# miniDCU.net
KiCad netlist of a schematic drawn in EAGLE
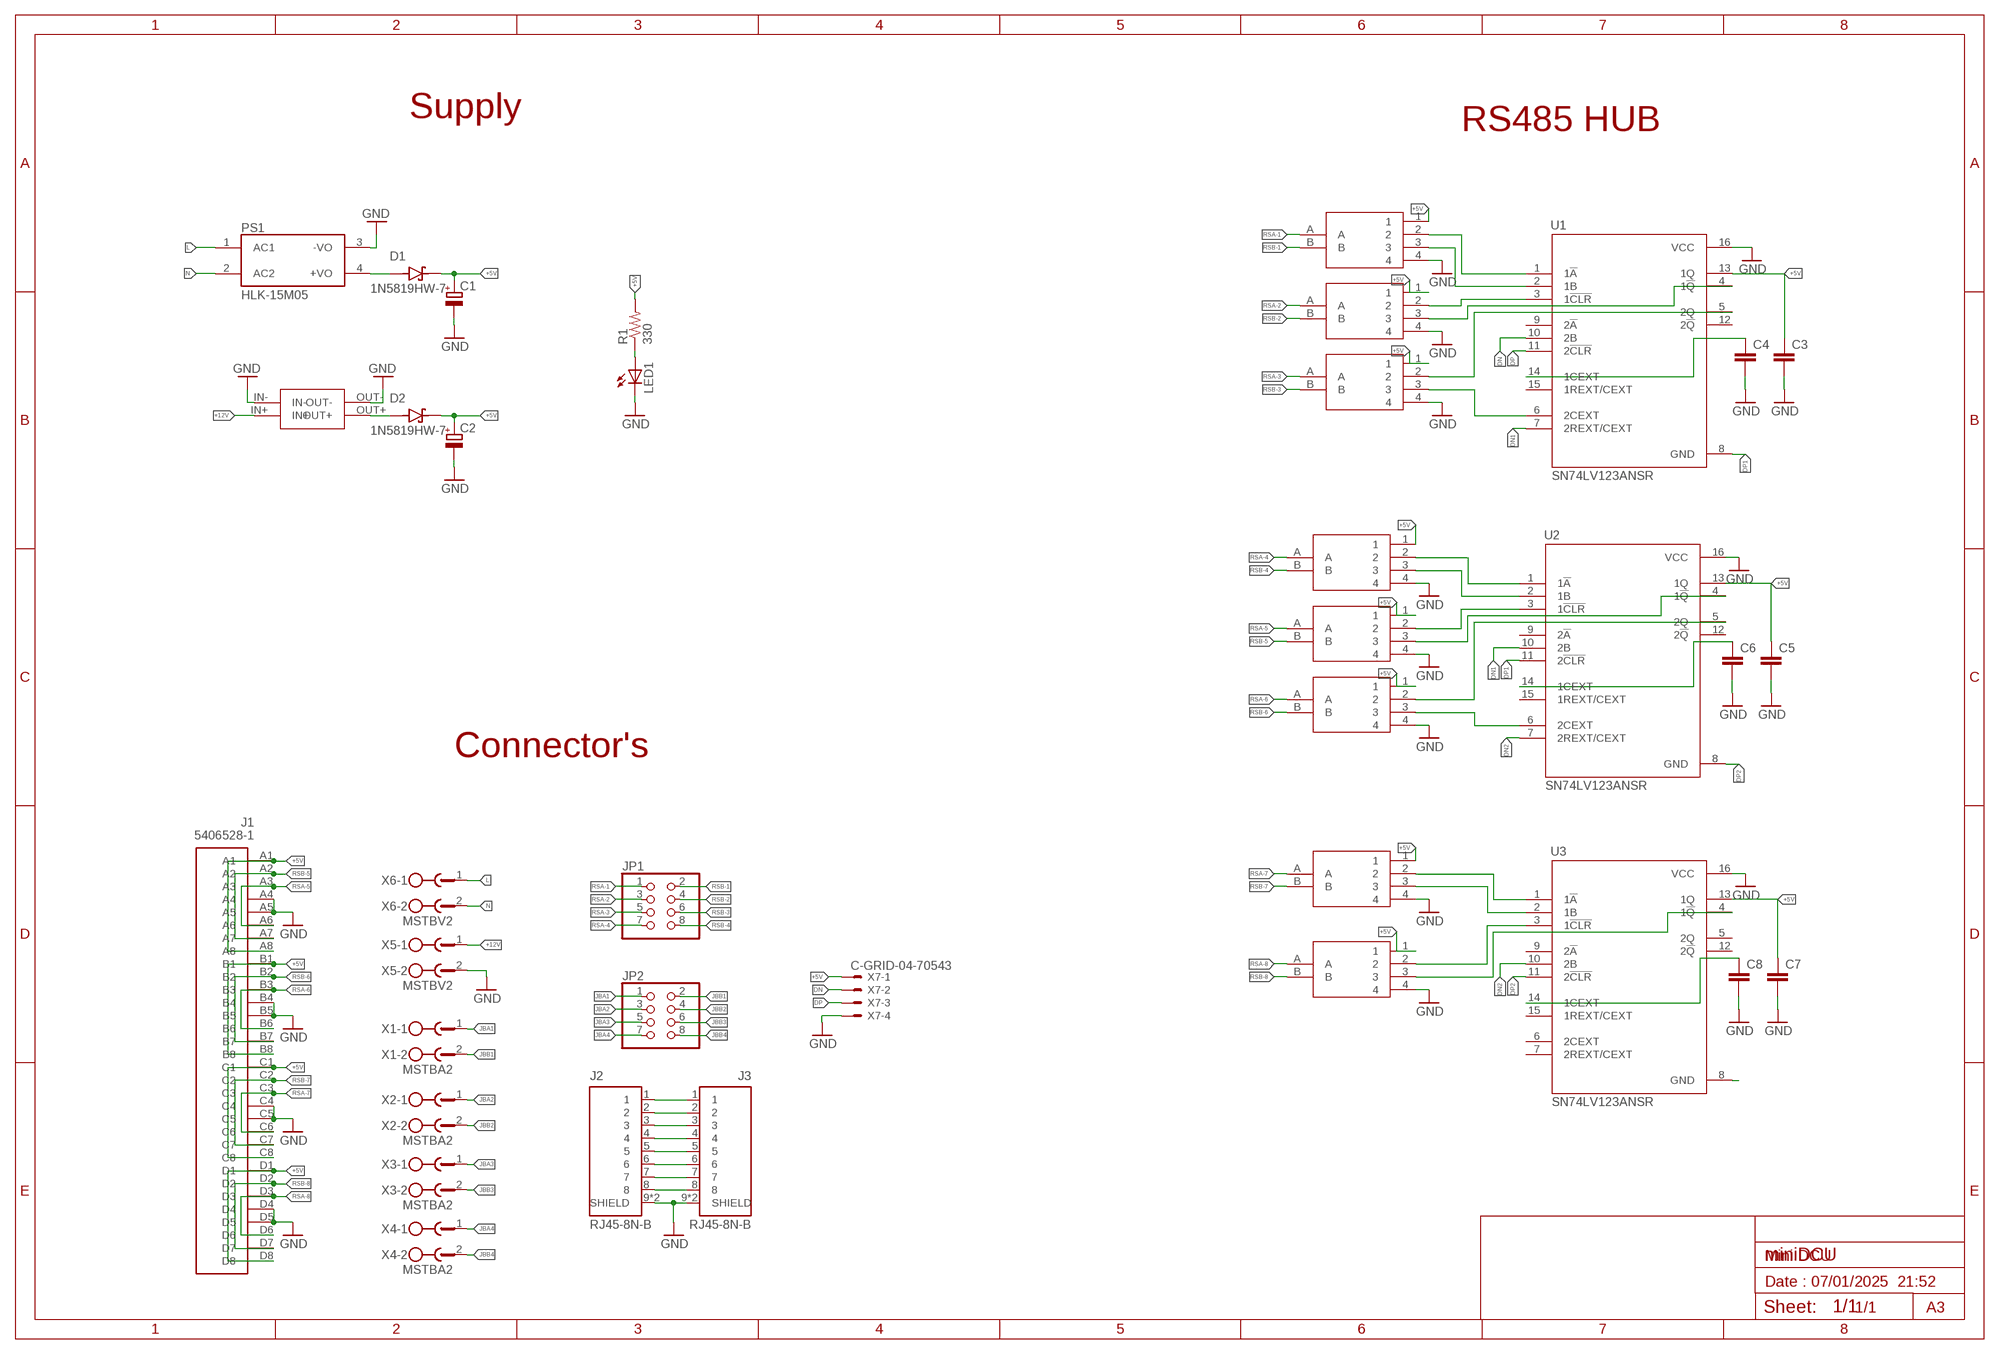
[diagram p0: schematic, sheet 1]

(export (version "E")
  (design (tool "Eeschema 10.0.6"))
  (components
    (comp (ref "C1")
      (value "CPOL-EU153CLV-0505")
      (footprint "eagle-import:153CLV-0505")
      (libsource (lib "eagle-import") (part "CPOL-EU153CLV-0505"))
    )
    (comp (ref "C2")
      (value "CPOL-EU153CLV-0505")
      (footprint "eagle-import:153CLV-0505")
      (libsource (lib "eagle-import") (part "CPOL-EU153CLV-0505"))
    )
    (comp (ref "C3")
      (value "C-EUC0603K")
      (footprint "eagle-import:C0603K")
      (libsource (lib "eagle-import") (part "C-EUC0603K"))
    )
    (comp (ref "C4")
      (value "C-EUC0603K")
      (footprint "eagle-import:C0603K")
      (libsource (lib "eagle-import") (part "C-EUC0603K"))
    )
    (comp (ref "C5")
      (value "C-EUC0603K")
      (footprint "eagle-import:C0603K")
      (libsource (lib "eagle-import") (part "C-EUC0603K"))
    )
    (comp (ref "C6")
      (value "C-EUC0603K")
      (footprint "eagle-import:C0603K")
      (libsource (lib "eagle-import") (part "C-EUC0603K"))
    )
    (comp (ref "C7")
      (value "C-EUC0603K")
      (footprint "eagle-import:C0603K")
      (libsource (lib "eagle-import") (part "C-EUC0603K"))
    )
    (comp (ref "C8")
      (value "C-EUC0603K")
      (footprint "eagle-import:C0603K")
      (libsource (lib "eagle-import") (part "C-EUC0603K"))
    )
    (comp (ref "D1")
      (value "1N5819HW-7")
      (footprint "eagle-import:SOD3715X145N")
      (fields (field (name "MF") "Diodes Inc."))
      (libsource (lib "eagle-import") (part "1N5819HW-7"))
    )
    (comp (ref "D2")
      (value "1N5819HW-7")
      (footprint "eagle-import:SOD3715X145N")
      (fields (field (name "MF") "Diodes Inc."))
      (libsource (lib "eagle-import") (part "1N5819HW-7"))
    )
    (comp (ref "J1")
      (value "5406528-1")
      (footprint "eagle-import:5406528-1")
      (fields (field (name "MF") "TE Connectivity"))
      (libsource (lib "eagle-import") (part "5406528-1"))
    )
    (comp (ref "J2")
      (value "RJ45-8N-B")
      (footprint "eagle-import:TE_RJ45-8N-B")
      (fields (field (name "MF") "TE Connectivity"))
      (libsource (lib "eagle-import") (part "RJ45-8N-B"))
    )
    (comp (ref "J3")
      (value "RJ45-8N-B")
      (footprint "eagle-import:TE_RJ45-8N-B")
      (fields (field (name "MF") "TE Connectivity"))
      (libsource (lib "eagle-import") (part "RJ45-8N-B"))
    )
    (comp (ref "JP1")
      (value "PINHD-2X4")
      (footprint "eagle-import:2X04")
      (libsource (lib "eagle-import") (part "PINHD-2X4"))
    )
    (comp (ref "JP2")
      (value "PINHD-2X4")
      (footprint "eagle-import:2X04")
      (libsource (lib "eagle-import") (part "PINHD-2X4"))
    )
    (comp (ref "LED1")
      (value "LED3MM")
      (footprint "eagle-import:LED3MM")
      (libsource (lib "eagle-import") (part "LED3MM"))
    )
    (comp (ref "MINI1")
      (value "MINI360")
      (footprint "eagle-import:MINI360")
      (libsource (lib "eagle-import") (part "MINI360"))
    )
    (comp (ref "PS1")
      (value "HLK-15M05")
      (footprint "eagle-import:CONV_HLK-15M05")
      (fields (field (name "MF") "Hi-link") (field (name "MP") "HLK-10M12"))
      (libsource (lib "eagle-import") (part "HLK-15M05"))
    )
    (comp (ref "R1")
      (value "330")
      (footprint "eagle-import:M0805")
      (libsource (lib "eagle-import") (part "R-US_M0805"))
    )
    (comp (ref "U1")
      (value "SN74LV123ANSR")
      (footprint "eagle-import:SOIC127P780X200-16N")
      (fields (field (name "DIGIKEY_PART_NUMBER") "296-46201-2-ND") (field (name "MF") "Texas Instruments"))
      (libsource (lib "eagle-import") (part "SN74LV123ANSR"))
    )
    (comp (ref "U2")
      (value "SN74LV123ANSR")
      (footprint "eagle-import:SOIC127P780X200-16N")
      (fields (field (name "DIGIKEY_PART_NUMBER") "296-46201-2-ND") (field (name "MF") "Texas Instruments"))
      (libsource (lib "eagle-import") (part "SN74LV123ANSR"))
    )
    (comp (ref "U3")
      (value "SN74LV123ANSR")
      (footprint "eagle-import:SOIC127P780X200-16N")
      (fields (field (name "DIGIKEY_PART_NUMBER") "296-46201-2-ND") (field (name "MF") "Texas Instruments"))
      (libsource (lib "eagle-import") (part "SN74LV123ANSR"))
    )
    (comp (ref "USB2RS1")
      (value "USB2RS485")
      (footprint "eagle-import:USB2RS485")
      (libsource (lib "eagle-import") (part "USB2RS485"))
    )
    (comp (ref "USB2RS2")
      (value "USB2RS485")
      (footprint "eagle-import:USB2RS485")
      (libsource (lib "eagle-import") (part "USB2RS485"))
    )
    (comp (ref "USB2RS3")
      (value "USB2RS485")
      (footprint "eagle-import:USB2RS485")
      (libsource (lib "eagle-import") (part "USB2RS485"))
    )
    (comp (ref "USB2RS4")
      (value "USB2RS485")
      (footprint "eagle-import:USB2RS485")
      (libsource (lib "eagle-import") (part "USB2RS485"))
    )
    (comp (ref "USB2RS5")
      (value "USB2RS485")
      (footprint "eagle-import:USB2RS485")
      (libsource (lib "eagle-import") (part "USB2RS485"))
    )
    (comp (ref "USB2RS6")
      (value "USB2RS485")
      (footprint "eagle-import:USB2RS485")
      (libsource (lib "eagle-import") (part "USB2RS485"))
    )
    (comp (ref "USB2RS7")
      (value "USB2RS485")
      (footprint "eagle-import:USB2RS485")
      (libsource (lib "eagle-import") (part "USB2RS485"))
    )
    (comp (ref "USB2RS8")
      (value "USB2RS485")
      (footprint "eagle-import:USB2RS485")
      (libsource (lib "eagle-import") (part "USB2RS485"))
    )
    (comp (ref "X1")
      (value "MSTBA2")
      (footprint "eagle-import:MSTBA2")
      (fields (field (name "MF") "FARNELL") (field (name "MPN") "1757242"))
      (libsource (lib "eagle-import") (part "MSTBA2"))
    )
    (comp (ref "X2")
      (value "MSTBA2")
      (footprint "eagle-import:MSTBA2")
      (fields (field (name "MF") "FARNELL") (field (name "MPN") "1757242"))
      (libsource (lib "eagle-import") (part "MSTBA2"))
    )
    (comp (ref "X3")
      (value "MSTBA2")
      (footprint "eagle-import:MSTBA2")
      (fields (field (name "MF") "FARNELL") (field (name "MPN") "1757242"))
      (libsource (lib "eagle-import") (part "MSTBA2"))
    )
    (comp (ref "X4")
      (value "MSTBA2")
      (footprint "eagle-import:MSTBA2")
      (fields (field (name "MF") "FARNELL") (field (name "MPN") "1757242"))
      (libsource (lib "eagle-import") (part "MSTBA2"))
    )
    (comp (ref "X5")
      (value "MSTBV2")
      (footprint "eagle-import:MSTBV2")
      (libsource (lib "eagle-import") (part "MSTBV2"))
    )
    (comp (ref "X6")
      (value "MSTBV2")
      (footprint "eagle-import:MSTBV2")
      (libsource (lib "eagle-import") (part "MSTBV2"))
    )
    (comp (ref "X7")
      (value "C-GRID-04-70543")
      (footprint "eagle-import:70543-04")
      (fields (field (name "MF") "MOLEX"))
      (libsource (lib "eagle-import") (part "C-GRID-04-70543"))
    )
  )
  (nets
    (net (code "1") (name "+5V") (class "Default")
      (node (ref "C1") (pin "+") (pinfunction "+_+") (pintype "passive"))
      (node (ref "C2") (pin "+") (pinfunction "+_+") (pintype "passive"))
      (node (ref "C3") (pin "1") (pinfunction "1_1") (pintype "passive"))
      (node (ref "C5") (pin "1") (pinfunction "1_1") (pintype "passive"))
      (node (ref "C7") (pin "1") (pinfunction "1_1") (pintype "passive"))
      (node (ref "D1") (pin "C") (pinfunction "K_C") (pintype "passive"))
      (node (ref "D2") (pin "C") (pinfunction "K_C") (pintype "passive"))
      (node (ref "J1") (pin "A1") (pinfunction "A1_A1") (pintype "bidirectional"))
      (node (ref "J1") (pin "A8") (pinfunction "A8_A8") (pintype "bidirectional"))
      (node (ref "J1") (pin "B1") (pinfunction "B1_B1") (pintype "bidirectional"))
      (node (ref "J1") (pin "B8") (pinfunction "B8_B8") (pintype "bidirectional"))
      (node (ref "J1") (pin "C1") (pinfunction "C1_C1") (pintype "bidirectional"))
      (node (ref "J1") (pin "C8") (pinfunction "C8_C8") (pintype "bidirectional"))
      (node (ref "J1") (pin "D1") (pinfunction "D1_D1") (pintype "bidirectional"))
      (node (ref "J1") (pin "D8") (pinfunction "D8_D8") (pintype "bidirectional"))
      (node (ref "R1") (pin "2") (pinfunction "2_2") (pintype "passive"))
      (node (ref "U1") (pin "13") (pinfunction "1Q_13") (pintype "output"))
      (node (ref "U2") (pin "13") (pinfunction "1Q_13") (pintype "output"))
      (node (ref "U3") (pin "13") (pinfunction "1Q_13") (pintype "output"))
      (node (ref "USB2RS1") (pin "1") (pinfunction "1_1") (pintype "bidirectional"))
      (node (ref "USB2RS2") (pin "1") (pinfunction "1_1") (pintype "bidirectional"))
      (node (ref "USB2RS3") (pin "1") (pinfunction "1_1") (pintype "bidirectional"))
      (node (ref "USB2RS4") (pin "1") (pinfunction "1_1") (pintype "bidirectional"))
      (node (ref "USB2RS5") (pin "1") (pinfunction "1_1") (pintype "bidirectional"))
      (node (ref "USB2RS6") (pin "1") (pinfunction "1_1") (pintype "bidirectional"))
      (node (ref "USB2RS7") (pin "1") (pinfunction "1_1") (pintype "bidirectional"))
      (node (ref "USB2RS8") (pin "1") (pinfunction "1_1") (pintype "bidirectional"))
      (node (ref "X7") (pin "1") (pinfunction "S_1") (pintype "passive"))
    )
    (net (code "2") (name "+12V") (class "Default")
      (node (ref "MINI1") (pin "IN+") (pinfunction "IN+_IN+") (pintype "bidirectional"))
      (node (ref "X5") (pin "1") (pinfunction "1_1") (pintype "passive"))
    )
    (net (code "3") (name "DN") (class "Default")
      (node (ref "U1") (pin "10") (pinfunction "2B_10") (pintype "input"))
      (node (ref "X7") (pin "2") (pinfunction "S_2") (pintype "passive"))
    )
    (net (code "4") (name "DN1") (class "Default")
      (node (ref "U1") (pin "7") (pinfunction "2REXT/CEXT_7") (pintype "bidirectional"))
      (node (ref "U2") (pin "10") (pinfunction "2B_10") (pintype "input"))
    )
    (net (code "5") (name "DN2") (class "Default")
      (node (ref "U2") (pin "7") (pinfunction "2REXT/CEXT_7") (pintype "bidirectional"))
      (node (ref "U3") (pin "10") (pinfunction "2B_10") (pintype "input"))
    )
    (net (code "6") (name "DP") (class "Default")
      (node (ref "U1") (pin "11") (pinfunction "2~{CLR}_11") (pintype "input"))
      (node (ref "X7") (pin "3") (pinfunction "S_3") (pintype "passive"))
    )
    (net (code "7") (name "DP1") (class "Default")
      (node (ref "U1") (pin "8") (pinfunction "GND_8") (pintype "power_in"))
      (node (ref "U2") (pin "11") (pinfunction "2~{CLR}_11") (pintype "input"))
    )
    (net (code "8") (name "DP2") (class "Default")
      (node (ref "U2") (pin "8") (pinfunction "GND_8") (pintype "power_in"))
      (node (ref "U3") (pin "11") (pinfunction "2~{CLR}_11") (pintype "input"))
    )
    (net (code "9") (name "GND") (class "Default")
      (node (ref "C1") (pin "-") (pinfunction "-_-") (pintype "passive"))
      (node (ref "C2") (pin "-") (pinfunction "-_-") (pintype "passive"))
      (node (ref "C3") (pin "2") (pinfunction "2_2") (pintype "passive"))
      (node (ref "C4") (pin "2") (pinfunction "2_2") (pintype "passive"))
      (node (ref "C5") (pin "2") (pinfunction "2_2") (pintype "passive"))
      (node (ref "C6") (pin "2") (pinfunction "2_2") (pintype "passive"))
      (node (ref "C7") (pin "2") (pinfunction "2_2") (pintype "passive"))
      (node (ref "C8") (pin "2") (pinfunction "2_2") (pintype "passive"))
      (node (ref "J1") (pin "A4") (pinfunction "A4_A4") (pintype "bidirectional"))
      (node (ref "J1") (pin "A5") (pinfunction "A5_A5") (pintype "bidirectional"))
      (node (ref "J1") (pin "B4") (pinfunction "B4_B4") (pintype "bidirectional"))
      (node (ref "J1") (pin "B5") (pinfunction "B5_B5") (pintype "bidirectional"))
      (node (ref "J1") (pin "C4") (pinfunction "C4_C4") (pintype "bidirectional"))
      (node (ref "J1") (pin "C5") (pinfunction "C5_C5") (pintype "bidirectional"))
      (node (ref "J1") (pin "D4") (pinfunction "D4_D4") (pintype "bidirectional"))
      (node (ref "J1") (pin "D5") (pinfunction "D5_D5") (pintype "bidirectional"))
      (node (ref "J2") (pin "10") (pinfunction "SHIELD_10") (pintype "passive"))
      (node (ref "J2") (pin "9") (pinfunction "SHIELD_9") (pintype "passive"))
      (node (ref "J3") (pin "10") (pinfunction "SHIELD_10") (pintype "passive"))
      (node (ref "J3") (pin "9") (pinfunction "SHIELD_9") (pintype "passive"))
      (node (ref "LED1") (pin "K") (pinfunction "C_K") (pintype "passive"))
      (node (ref "MINI1") (pin "IN-") (pinfunction "IN-_IN-") (pintype "bidirectional"))
      (node (ref "MINI1") (pin "OUT-") (pinfunction "OUT-_OUT-") (pintype "bidirectional"))
      (node (ref "PS1") (pin "3") (pinfunction "-VO_3") (pintype "output"))
      (node (ref "U1") (pin "16") (pinfunction "VCC_16") (pintype "power_in"))
      (node (ref "U2") (pin "16") (pinfunction "VCC_16") (pintype "power_in"))
      (node (ref "U3") (pin "16") (pinfunction "VCC_16") (pintype "power_in"))
      (node (ref "USB2RS1") (pin "4") (pinfunction "4_4") (pintype "bidirectional"))
      (node (ref "USB2RS2") (pin "4") (pinfunction "4_4") (pintype "bidirectional"))
      (node (ref "USB2RS3") (pin "4") (pinfunction "4_4") (pintype "bidirectional"))
      (node (ref "USB2RS4") (pin "4") (pinfunction "4_4") (pintype "bidirectional"))
      (node (ref "USB2RS5") (pin "4") (pinfunction "4_4") (pintype "bidirectional"))
      (node (ref "USB2RS6") (pin "4") (pinfunction "4_4") (pintype "bidirectional"))
      (node (ref "USB2RS7") (pin "4") (pinfunction "4_4") (pintype "bidirectional"))
      (node (ref "USB2RS8") (pin "4") (pinfunction "4_4") (pintype "bidirectional"))
      (node (ref "X5") (pin "2") (pinfunction "1_2") (pintype "passive"))
      (node (ref "X7") (pin "4") (pinfunction "S_4") (pintype "passive"))
    )
    (net (code "10") (name "JBA1") (class "Default")
      (node (ref "JP2") (pin "1") (pinfunction "1_1") (pintype "passive"))
      (node (ref "X1") (pin "1") (pinfunction "1_1") (pintype "passive"))
    )
    (net (code "11") (name "JBA2") (class "Default")
      (node (ref "JP2") (pin "3") (pinfunction "3_3") (pintype "passive"))
      (node (ref "X2") (pin "1") (pinfunction "1_1") (pintype "passive"))
    )
    (net (code "12") (name "JBA3") (class "Default")
      (node (ref "JP2") (pin "5") (pinfunction "5_5") (pintype "passive"))
      (node (ref "X3") (pin "1") (pinfunction "1_1") (pintype "passive"))
    )
    (net (code "13") (name "JBA4") (class "Default")
      (node (ref "JP2") (pin "7") (pinfunction "7_7") (pintype "passive"))
      (node (ref "X4") (pin "1") (pinfunction "1_1") (pintype "passive"))
    )
    (net (code "14") (name "JBB1") (class "Default")
      (node (ref "JP2") (pin "2") (pinfunction "2_2") (pintype "passive"))
      (node (ref "X1") (pin "2") (pinfunction "1_2") (pintype "passive"))
    )
    (net (code "15") (name "JBB2") (class "Default")
      (node (ref "JP2") (pin "4") (pinfunction "4_4") (pintype "passive"))
      (node (ref "X2") (pin "2") (pinfunction "1_2") (pintype "passive"))
    )
    (net (code "16") (name "JBB3") (class "Default")
      (node (ref "JP2") (pin "6") (pinfunction "6_6") (pintype "passive"))
      (node (ref "X3") (pin "2") (pinfunction "1_2") (pintype "passive"))
    )
    (net (code "17") (name "JBB4") (class "Default")
      (node (ref "JP2") (pin "8") (pinfunction "8_8") (pintype "passive"))
      (node (ref "X4") (pin "2") (pinfunction "1_2") (pintype "passive"))
    )
    (net (code "18") (name "L") (class "Default")
      (node (ref "PS1") (pin "1") (pinfunction "AC1_1") (pintype "input"))
      (node (ref "X6") (pin "1") (pinfunction "1_1") (pintype "passive"))
    )
    (net (code "19") (name "N") (class "Default")
      (node (ref "PS1") (pin "2") (pinfunction "AC2_2") (pintype "input"))
      (node (ref "X6") (pin "2") (pinfunction "1_2") (pintype "passive"))
    )
    (net (code "20") (name "Net-(D2-PadA)") (class "Default")
      (node (ref "D2") (pin "A") (pinfunction "A_A") (pintype "passive"))
      (node (ref "MINI1") (pin "OUT+") (pinfunction "OUT+_OUT+") (pintype "bidirectional"))
    )
    (net (code "21") (name "Net-(J2-Pad1)") (class "Default")
      (node (ref "J2") (pin "1") (pinfunction "1_1") (pintype "passive"))
      (node (ref "J3") (pin "1") (pinfunction "1_1") (pintype "passive"))
    )
    (net (code "22") (name "Net-(J2-Pad2)") (class "Default")
      (node (ref "J2") (pin "2") (pinfunction "2_2") (pintype "passive"))
      (node (ref "J3") (pin "2") (pinfunction "2_2") (pintype "passive"))
    )
    (net (code "23") (name "Net-(J2-Pad3)") (class "Default")
      (node (ref "J2") (pin "3") (pinfunction "3_3") (pintype "passive"))
      (node (ref "J3") (pin "3") (pinfunction "3_3") (pintype "passive"))
    )
    (net (code "24") (name "Net-(J2-Pad4)") (class "Default")
      (node (ref "J2") (pin "4") (pinfunction "4_4") (pintype "passive"))
      (node (ref "J3") (pin "4") (pinfunction "4_4") (pintype "passive"))
    )
    (net (code "25") (name "Net-(J2-Pad5)") (class "Default")
      (node (ref "J2") (pin "5") (pinfunction "5_5") (pintype "passive"))
      (node (ref "J3") (pin "5") (pinfunction "5_5") (pintype "passive"))
    )
    (net (code "26") (name "Net-(J2-Pad6)") (class "Default")
      (node (ref "J2") (pin "6") (pinfunction "6_6") (pintype "passive"))
      (node (ref "J3") (pin "6") (pinfunction "6_6") (pintype "passive"))
    )
    (net (code "27") (name "Net-(J2-Pad7)") (class "Default")
      (node (ref "J2") (pin "7") (pinfunction "7_7") (pintype "passive"))
      (node (ref "J3") (pin "7") (pinfunction "7_7") (pintype "passive"))
    )
    (net (code "28") (name "Net-(J2-Pad8)") (class "Default")
      (node (ref "J2") (pin "8") (pinfunction "8_8") (pintype "passive"))
      (node (ref "J3") (pin "8") (pinfunction "8_8") (pintype "passive"))
    )
    (net (code "29") (name "Net-(LED1-PadA)") (class "Default")
      (node (ref "LED1") (pin "A") (pinfunction "A_A") (pintype "passive"))
      (node (ref "R1") (pin "1") (pinfunction "1_1") (pintype "passive"))
    )
    (net (code "30") (name "Net-(PS1-+VO)") (class "Default")
      (node (ref "D1") (pin "A") (pinfunction "A_A") (pintype "passive"))
      (node (ref "PS1") (pin "4") (pinfunction "+VO_4") (pintype "output"))
    )
    (net (code "31") (name "Net-(U1-1B)") (class "Default")
      (node (ref "U1") (pin "2") (pinfunction "1B_2") (pintype "input"))
      (node (ref "USB2RS1") (pin "3") (pinfunction "3_3") (pintype "bidirectional"))
    )
    (net (code "32") (name "Net-(U1-1CEXT)") (class "Default")
      (node (ref "C4") (pin "1") (pinfunction "1_1") (pintype "passive"))
      (node (ref "U1") (pin "14") (pinfunction "1CEXT_14") (pintype "bidirectional"))
    )
    (net (code "33") (name "Net-(U1-1~{A})") (class "Default")
      (node (ref "U1") (pin "1") (pinfunction "1~{A}_1") (pintype "input"))
      (node (ref "USB2RS1") (pin "2") (pinfunction "2_2") (pintype "bidirectional"))
    )
    (net (code "34") (name "Net-(U1-1~{CLR})") (class "Default")
      (node (ref "U1") (pin "3") (pinfunction "1~{CLR}_3") (pintype "input"))
      (node (ref "USB2RS2") (pin "2") (pinfunction "2_2") (pintype "bidirectional"))
    )
    (net (code "35") (name "Net-(U1-1~{Q})") (class "Default")
      (node (ref "U1") (pin "4") (pinfunction "1~{Q}_4") (pintype "output"))
      (node (ref "USB2RS2") (pin "3") (pinfunction "3_3") (pintype "bidirectional"))
    )
    (net (code "36") (name "Net-(U1-2CEXT)") (class "Default")
      (node (ref "U1") (pin "6") (pinfunction "2CEXT_6") (pintype "bidirectional"))
      (node (ref "USB2RS3") (pin "3") (pinfunction "3_3") (pintype "bidirectional"))
    )
    (net (code "37") (name "Net-(U1-2Q)") (class "Default")
      (node (ref "U1") (pin "5") (pinfunction "2Q_5") (pintype "output"))
      (node (ref "USB2RS3") (pin "2") (pinfunction "2_2") (pintype "bidirectional"))
    )
    (net (code "38") (name "Net-(U2-1B)") (class "Default")
      (node (ref "U2") (pin "2") (pinfunction "1B_2") (pintype "input"))
      (node (ref "USB2RS5") (pin "3") (pinfunction "3_3") (pintype "bidirectional"))
    )
    (net (code "39") (name "Net-(U2-1CEXT)") (class "Default")
      (node (ref "C6") (pin "1") (pinfunction "1_1") (pintype "passive"))
      (node (ref "U2") (pin "14") (pinfunction "1CEXT_14") (pintype "bidirectional"))
    )
    (net (code "40") (name "Net-(U2-1~{A})") (class "Default")
      (node (ref "U2") (pin "1") (pinfunction "1~{A}_1") (pintype "input"))
      (node (ref "USB2RS5") (pin "2") (pinfunction "2_2") (pintype "bidirectional"))
    )
    (net (code "41") (name "Net-(U2-1~{CLR})") (class "Default")
      (node (ref "U2") (pin "3") (pinfunction "1~{CLR}_3") (pintype "input"))
      (node (ref "USB2RS6") (pin "2") (pinfunction "2_2") (pintype "bidirectional"))
    )
    (net (code "42") (name "Net-(U2-1~{Q})") (class "Default")
      (node (ref "U2") (pin "4") (pinfunction "1~{Q}_4") (pintype "output"))
      (node (ref "USB2RS6") (pin "3") (pinfunction "3_3") (pintype "bidirectional"))
    )
    (net (code "43") (name "Net-(U2-2CEXT)") (class "Default")
      (node (ref "U2") (pin "6") (pinfunction "2CEXT_6") (pintype "bidirectional"))
      (node (ref "USB2RS7") (pin "3") (pinfunction "3_3") (pintype "bidirectional"))
    )
    (net (code "44") (name "Net-(U2-2Q)") (class "Default")
      (node (ref "U2") (pin "5") (pinfunction "2Q_5") (pintype "output"))
      (node (ref "USB2RS7") (pin "2") (pinfunction "2_2") (pintype "bidirectional"))
    )
    (net (code "45") (name "Net-(U3-1B)") (class "Default")
      (node (ref "U3") (pin "2") (pinfunction "1B_2") (pintype "input"))
      (node (ref "USB2RS4") (pin "3") (pinfunction "3_3") (pintype "bidirectional"))
    )
    (net (code "46") (name "Net-(U3-1CEXT)") (class "Default")
      (node (ref "C8") (pin "1") (pinfunction "1_1") (pintype "passive"))
      (node (ref "U3") (pin "14") (pinfunction "1CEXT_14") (pintype "bidirectional"))
    )
    (net (code "47") (name "Net-(U3-1~{A})") (class "Default")
      (node (ref "U3") (pin "1") (pinfunction "1~{A}_1") (pintype "input"))
      (node (ref "USB2RS4") (pin "2") (pinfunction "2_2") (pintype "bidirectional"))
    )
    (net (code "48") (name "Net-(U3-1~{CLR})") (class "Default")
      (node (ref "U3") (pin "3") (pinfunction "1~{CLR}_3") (pintype "input"))
      (node (ref "USB2RS8") (pin "2") (pinfunction "2_2") (pintype "bidirectional"))
    )
    (net (code "49") (name "Net-(U3-1~{Q})") (class "Default")
      (node (ref "U3") (pin "4") (pinfunction "1~{Q}_4") (pintype "output"))
      (node (ref "USB2RS8") (pin "3") (pinfunction "3_3") (pintype "bidirectional"))
    )
    (net (code "50") (name "RSA-1") (class "Default")
      (node (ref "JP1") (pin "1") (pinfunction "1_1") (pintype "passive"))
      (node (ref "USB2RS1") (pin "A") (pinfunction "A_A") (pintype "bidirectional"))
    )
    (net (code "51") (name "RSA-2") (class "Default")
      (node (ref "JP1") (pin "3") (pinfunction "3_3") (pintype "passive"))
      (node (ref "USB2RS2") (pin "A") (pinfunction "A_A") (pintype "bidirectional"))
    )
    (net (code "52") (name "RSA-3") (class "Default")
      (node (ref "JP1") (pin "5") (pinfunction "5_5") (pintype "passive"))
      (node (ref "USB2RS3") (pin "A") (pinfunction "A_A") (pintype "bidirectional"))
    )
    (net (code "53") (name "RSA-4") (class "Default")
      (node (ref "JP1") (pin "7") (pinfunction "7_7") (pintype "passive"))
      (node (ref "USB2RS5") (pin "A") (pinfunction "A_A") (pintype "bidirectional"))
    )
    (net (code "54") (name "RSA-5") (class "Default")
      (node (ref "J1") (pin "A3") (pinfunction "A3_A3") (pintype "bidirectional"))
      (node (ref "J1") (pin "A6") (pinfunction "A6_A6") (pintype "bidirectional"))
      (node (ref "USB2RS6") (pin "A") (pinfunction "A_A") (pintype "bidirectional"))
    )
    (net (code "55") (name "RSA-6") (class "Default")
      (node (ref "J1") (pin "B3") (pinfunction "B3_B3") (pintype "bidirectional"))
      (node (ref "J1") (pin "B6") (pinfunction "B6_B6") (pintype "bidirectional"))
      (node (ref "USB2RS7") (pin "A") (pinfunction "A_A") (pintype "bidirectional"))
    )
    (net (code "56") (name "RSA-7") (class "Default")
      (node (ref "J1") (pin "C3") (pinfunction "C3_C3") (pintype "bidirectional"))
      (node (ref "J1") (pin "C6") (pinfunction "C6_C6") (pintype "bidirectional"))
      (node (ref "USB2RS4") (pin "A") (pinfunction "A_A") (pintype "bidirectional"))
    )
    (net (code "57") (name "RSA-8") (class "Default")
      (node (ref "J1") (pin "D3") (pinfunction "D3_D3") (pintype "bidirectional"))
      (node (ref "J1") (pin "D6") (pinfunction "D6_D6") (pintype "bidirectional"))
      (node (ref "USB2RS8") (pin "A") (pinfunction "A_A") (pintype "bidirectional"))
    )
    (net (code "58") (name "RSB-1") (class "Default")
      (node (ref "JP1") (pin "2") (pinfunction "2_2") (pintype "passive"))
      (node (ref "USB2RS1") (pin "B") (pinfunction "B_B") (pintype "bidirectional"))
    )
    (net (code "59") (name "RSB-2") (class "Default")
      (node (ref "JP1") (pin "4") (pinfunction "4_4") (pintype "passive"))
      (node (ref "USB2RS2") (pin "B") (pinfunction "B_B") (pintype "bidirectional"))
    )
    (net (code "60") (name "RSB-3") (class "Default")
      (node (ref "JP1") (pin "6") (pinfunction "6_6") (pintype "passive"))
      (node (ref "USB2RS3") (pin "B") (pinfunction "B_B") (pintype "bidirectional"))
    )
    (net (code "61") (name "RSB-4") (class "Default")
      (node (ref "JP1") (pin "8") (pinfunction "8_8") (pintype "passive"))
      (node (ref "USB2RS5") (pin "B") (pinfunction "B_B") (pintype "bidirectional"))
    )
    (net (code "62") (name "RSB-5") (class "Default")
      (node (ref "J1") (pin "A2") (pinfunction "A2_A2") (pintype "bidirectional"))
      (node (ref "J1") (pin "A7") (pinfunction "A7_A7") (pintype "bidirectional"))
      (node (ref "USB2RS6") (pin "B") (pinfunction "B_B") (pintype "bidirectional"))
    )
    (net (code "63") (name "RSB-6") (class "Default")
      (node (ref "J1") (pin "B2") (pinfunction "B2_B2") (pintype "bidirectional"))
      (node (ref "J1") (pin "B7") (pinfunction "B7_B7") (pintype "bidirectional"))
      (node (ref "USB2RS7") (pin "B") (pinfunction "B_B") (pintype "bidirectional"))
    )
    (net (code "64") (name "RSB-7") (class "Default")
      (node (ref "J1") (pin "C2") (pinfunction "C2_C2") (pintype "bidirectional"))
      (node (ref "J1") (pin "C7") (pinfunction "C7_C7") (pintype "bidirectional"))
      (node (ref "USB2RS4") (pin "B") (pinfunction "B_B") (pintype "bidirectional"))
    )
    (net (code "65") (name "RSB-8") (class "Default")
      (node (ref "J1") (pin "D2") (pinfunction "D2_D2") (pintype "bidirectional"))
      (node (ref "J1") (pin "D7") (pinfunction "D7_D7") (pintype "bidirectional"))
      (node (ref "USB2RS8") (pin "B") (pinfunction "B_B") (pintype "bidirectional"))
    )
    (net (code "66") (name "unconnected-(U1-1REXT{slash}CEXT-Pad15)") (class "Default")
      (node (ref "U1") (pin "15") (pinfunction "1REXT/CEXT_15") (pintype "bidirectional"))
    )
    (net (code "67") (name "unconnected-(U1-2~{A}-Pad9)") (class "Default")
      (node (ref "U1") (pin "9") (pinfunction "2~{A}_9") (pintype "input"))
    )
    (net (code "68") (name "unconnected-(U1-2~{Q}-Pad12)") (class "Default")
      (node (ref "U1") (pin "12") (pinfunction "2~{Q}_12") (pintype "output"))
    )
    (net (code "69") (name "unconnected-(U2-1REXT{slash}CEXT-Pad15)") (class "Default")
      (node (ref "U2") (pin "15") (pinfunction "1REXT/CEXT_15") (pintype "bidirectional"))
    )
    (net (code "70") (name "unconnected-(U2-2~{A}-Pad9)") (class "Default")
      (node (ref "U2") (pin "9") (pinfunction "2~{A}_9") (pintype "input"))
    )
    (net (code "71") (name "unconnected-(U2-2~{Q}-Pad12)") (class "Default")
      (node (ref "U2") (pin "12") (pinfunction "2~{Q}_12") (pintype "output"))
    )
    (net (code "72") (name "unconnected-(U3-1REXT{slash}CEXT-Pad15)") (class "Default")
      (node (ref "U3") (pin "15") (pinfunction "1REXT/CEXT_15") (pintype "bidirectional"))
    )
    (net (code "73") (name "unconnected-(U3-2CEXT-Pad6)") (class "Default")
      (node (ref "U3") (pin "6") (pinfunction "2CEXT_6") (pintype "bidirectional"))
    )
    (net (code "74") (name "unconnected-(U3-2Q-Pad5)") (class "Default")
      (node (ref "U3") (pin "5") (pinfunction "2Q_5") (pintype "output"))
    )
    (net (code "75") (name "unconnected-(U3-2REXT{slash}CEXT-Pad7)") (class "Default")
      (node (ref "U3") (pin "7") (pinfunction "2REXT/CEXT_7") (pintype "bidirectional"))
    )
    (net (code "76") (name "unconnected-(U3-2~{A}-Pad9)") (class "Default")
      (node (ref "U3") (pin "9") (pinfunction "2~{A}_9") (pintype "input"))
    )
    (net (code "77") (name "unconnected-(U3-2~{Q}-Pad12)") (class "Default")
      (node (ref "U3") (pin "12") (pinfunction "2~{Q}_12") (pintype "output"))
    )
    (net (code "78") (name "unconnected-(U3-GND-Pad8)") (class "Default")
      (node (ref "U3") (pin "8") (pinfunction "GND_8") (pintype "power_in"))
    )
  )
)
